# t1-power2.net
KiCad netlist of a schematic drawn in Altium Designer
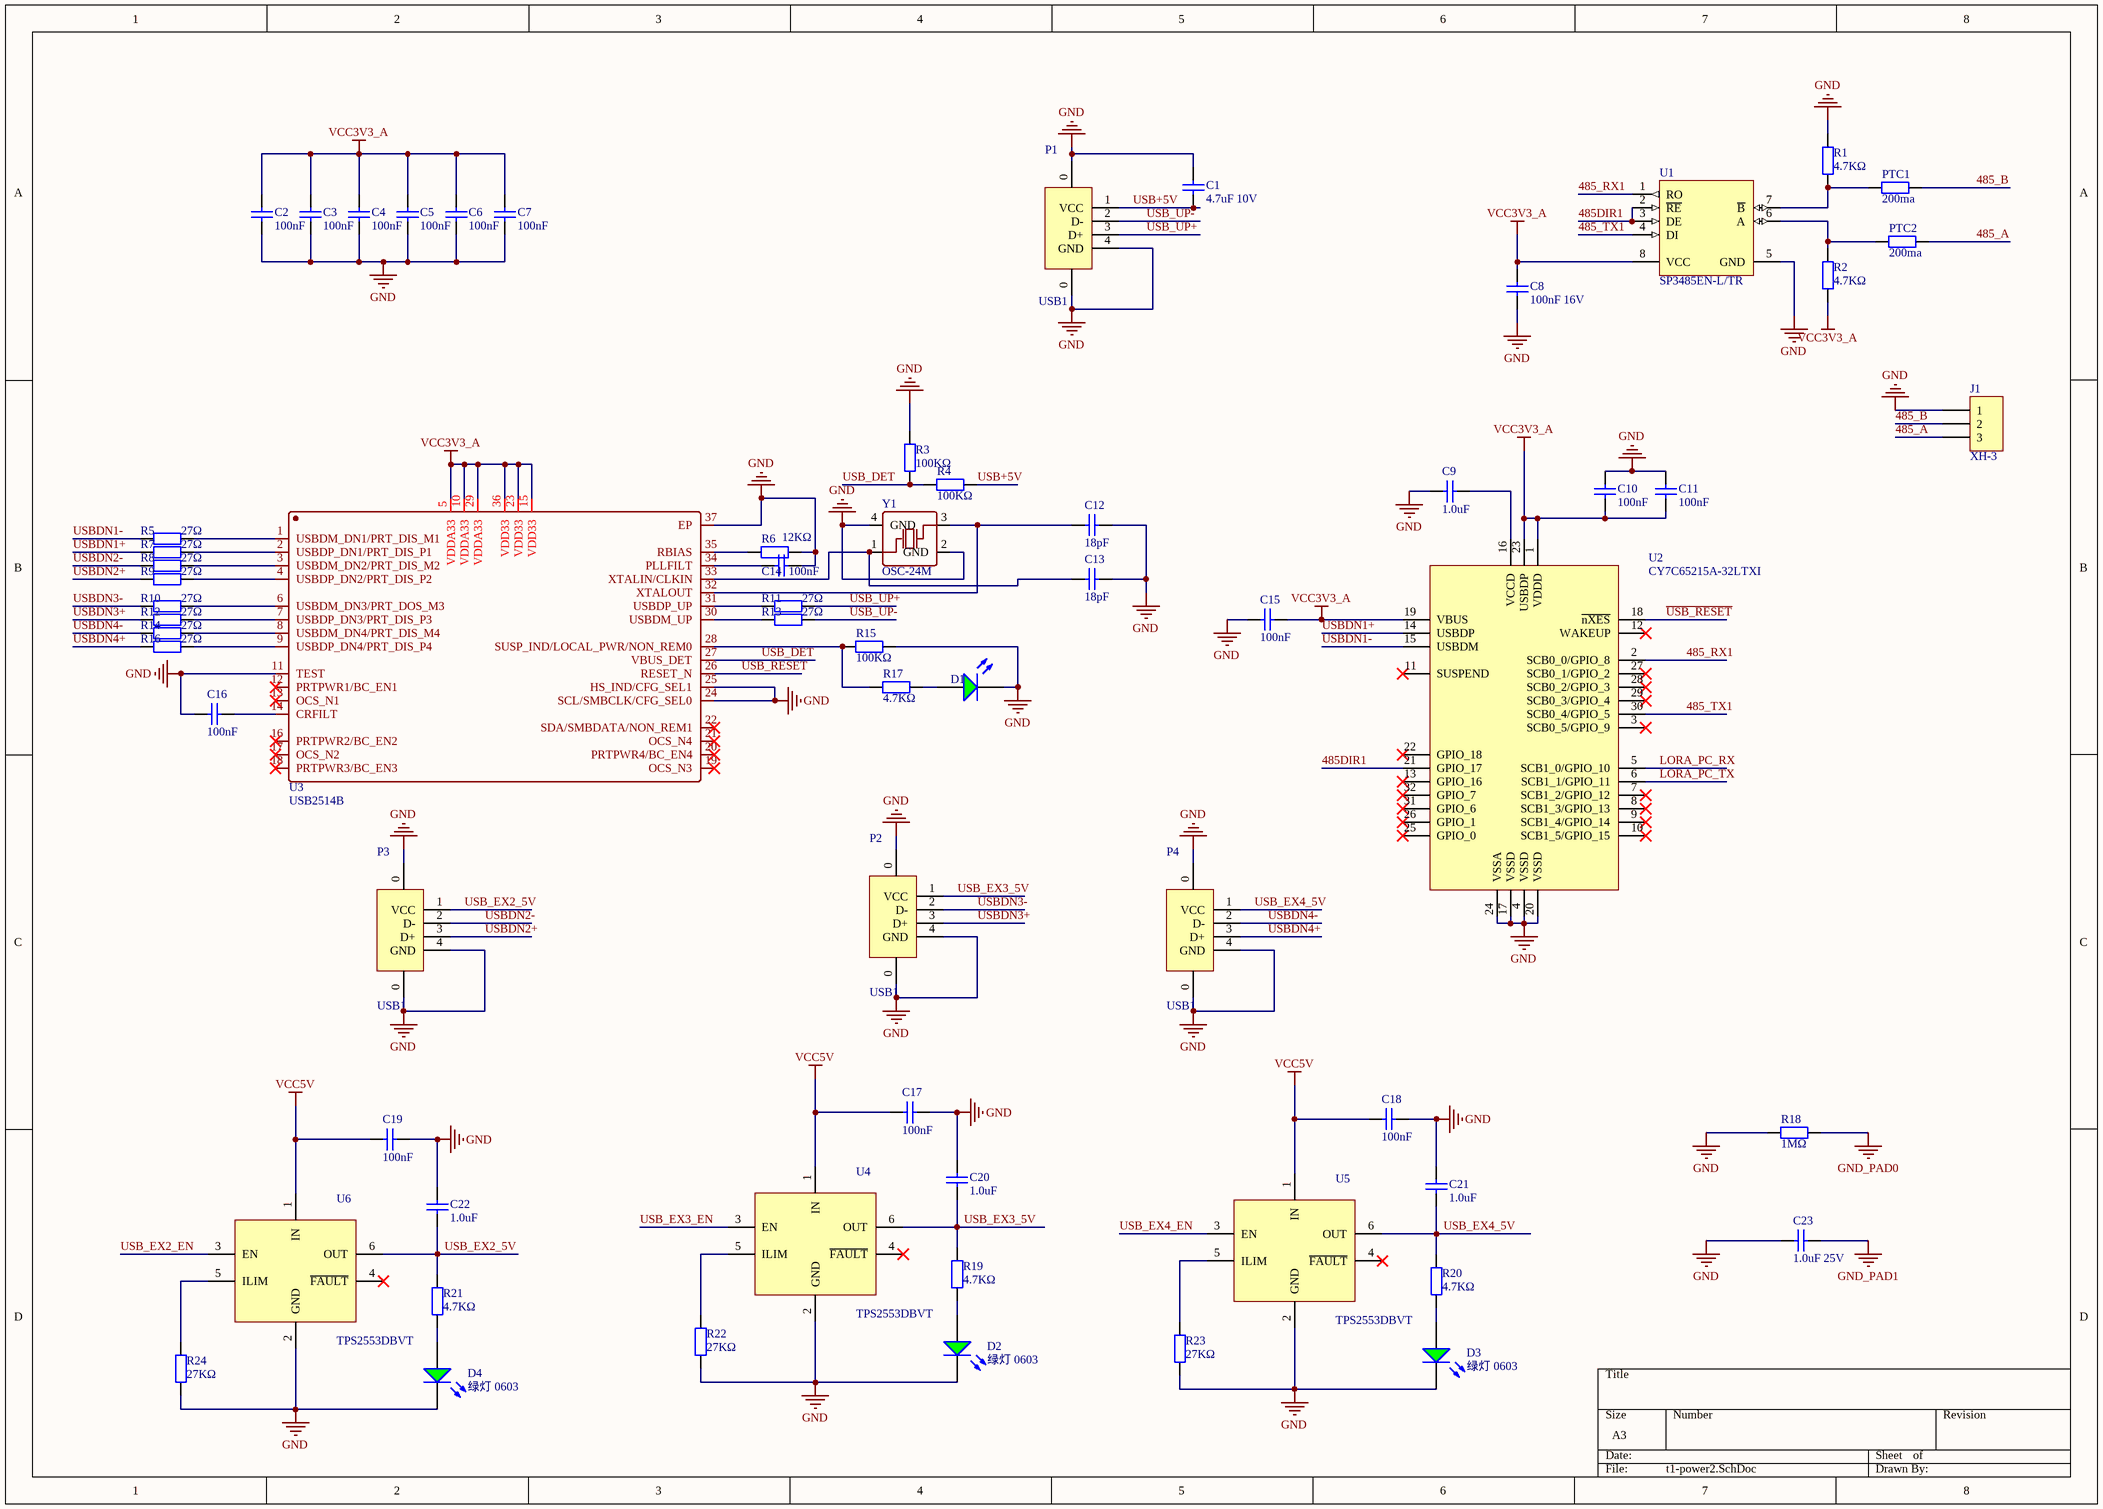
[diagram p0: t1-power2.SchDoc]

(export (version "E")
  (design (tool "Eeschema 10.0.6"))
  (components
    (comp (ref "C1")
      (value "4.7uF 10V")
      (footprint "0402_C")
      (description "贴片电容")
      (libsource (lib "AD封装2018.9.19Miscellaneous Devices LC") (part "0402 4.7uF (475) 20% 10V"))
    )
    (comp (ref "C2")
      (value "100nF")
      (footprint "0402_C")
      (description "贴片电容")
      (libsource (lib "AD封装2018.9.19Miscellaneous Devices LC") (part "0402 100nF (104) 10% 16V"))
    )
    (comp (ref "C3")
      (value "100nF")
      (footprint "0402_C")
      (description "贴片电容")
      (libsource (lib "AD封装2018.9.19Miscellaneous Devices LC") (part "0402 100nF (104) 10% 16V"))
    )
    (comp (ref "C4")
      (value "100nF")
      (footprint "0402_C")
      (description "贴片电容")
      (libsource (lib "AD封装2018.9.19Miscellaneous Devices LC") (part "0402 100nF (104) 10% 16V"))
    )
    (comp (ref "C5")
      (value "100nF")
      (footprint "0402_C")
      (description "贴片电容")
      (libsource (lib "AD封装2018.9.19Miscellaneous Devices LC") (part "0402 100nF (104) 10% 16V"))
    )
    (comp (ref "C6")
      (value "100nF")
      (footprint "0402_C")
      (description "贴片电容")
      (libsource (lib "AD封装2018.9.19Miscellaneous Devices LC") (part "0402 100nF (104) 10% 16V"))
    )
    (comp (ref "C7")
      (value "100nF")
      (footprint "0402_C")
      (description "贴片电容")
      (libsource (lib "AD封装2018.9.19Miscellaneous Devices LC") (part "0402 100nF (104) 10% 16V"))
    )
    (comp (ref "C8")
      (value "100nF 16V")
      (footprint "0402_C")
      (description "贴片电容")
      (libsource (lib "AD封装2018.9.19Miscellaneous Devices LC") (part "0402 100nF (104) 10% 16V"))
    )
    (comp (ref "C9")
      (value "1.0uF")
      (footprint "0402_C")
      (description "贴片电容")
      (libsource (lib "AD封装2018.9.19Miscellaneous Devices LC") (part "0402 1.0uF (105) 10% 25V"))
    )
    (comp (ref "C10")
      (value "100nF")
      (footprint "0402_C")
      (description "贴片电容")
      (libsource (lib "AD封装2018.9.19Miscellaneous Devices LC") (part "0402 100nF (104) 10% 16V"))
    )
    (comp (ref "C11")
      (value "100nF")
      (footprint "0402_C")
      (description "贴片电容")
      (libsource (lib "AD封装2018.9.19Miscellaneous Devices LC") (part "0402 100nF (104) 10% 16V"))
    )
    (comp (ref "C12")
      (value "18pF")
      (footprint "0402_C")
      (description "贴片电容")
      (libsource (lib "AD封装2018.9.19Miscellaneous Devices LC") (part "0402 18pF (180) 5% 50V"))
    )
    (comp (ref "C13")
      (value "18pF")
      (footprint "0402_C")
      (description "贴片电容")
      (libsource (lib "AD封装2018.9.19Miscellaneous Devices LC") (part "0402 18pF (180) 5% 50V"))
    )
    (comp (ref "C14")
      (value "100nF")
      (footprint "0402_C")
      (description "贴片电容")
      (libsource (lib "AD封装2018.9.19Miscellaneous Devices LC") (part "0402 100nF (104) 10% 16V"))
    )
    (comp (ref "C15")
      (value "100nF")
      (footprint "0402_C")
      (description "贴片电容")
      (libsource (lib "AD封装2018.9.19Miscellaneous Devices LC") (part "0402 100nF (104) 10% 16V"))
    )
    (comp (ref "C16")
      (value "100nF")
      (footprint "0402_C")
      (description "贴片电容")
      (libsource (lib "AD封装2018.9.19Miscellaneous Devices LC") (part "0402 100nF (104) 10% 16V"))
    )
    (comp (ref "C17")
      (value "100nF")
      (footprint "0402_C")
      (description "贴片电容")
      (libsource (lib "AD封装2018.9.19Miscellaneous Devices LC") (part "0402 100nF (104) 10% 16V"))
    )
    (comp (ref "C18")
      (value "100nF")
      (footprint "0402_C")
      (description "贴片电容")
      (libsource (lib "AD封装2018.9.19Miscellaneous Devices LC") (part "0402 100nF (104) 10% 16V"))
    )
    (comp (ref "C19")
      (value "100nF")
      (footprint "0402_C")
      (description "贴片电容")
      (libsource (lib "AD封装2018.9.19Miscellaneous Devices LC") (part "0402 100nF (104) 10% 16V"))
    )
    (comp (ref "C20")
      (value "1.0uF")
      (footprint "0402_C")
      (description "贴片电容")
      (libsource (lib "AD封装2018.9.19Miscellaneous Devices LC") (part "0402 1.0uF (105) 10% 25V"))
    )
    (comp (ref "C21")
      (value "1.0uF")
      (footprint "0402_C")
      (description "贴片电容")
      (libsource (lib "AD封装2018.9.19Miscellaneous Devices LC") (part "0402 1.0uF (105) 10% 25V"))
    )
    (comp (ref "C22")
      (value "1.0uF")
      (footprint "0402_C")
      (description "贴片电容")
      (libsource (lib "AD封装2018.9.19Miscellaneous Devices LC") (part "0402 1.0uF (105) 10% 25V"))
    )
    (comp (ref "C23")
      (value "1.0uF 25V")
      (footprint "0402_C")
      (description "贴片电容")
      (libsource (lib "AD封装2018.9.19Miscellaneous Devices LC") (part "0402 1.0uF (105) 10% 25V"))
    )
    (comp (ref "D1")
      (value "绿灯 0603")
      (footprint "0603_LED_S1")
      (description "发光二极管")
      (libsource (lib "AD封装2018.9.19Miscellaneous Devices LC") (part "0603 绿灯"))
    )
    (comp (ref "D2")
      (value "绿灯 0603")
      (footprint "0603_LED_S1")
      (description "发光二极管")
      (libsource (lib "AD封装2018.9.19Miscellaneous Devices LC") (part "0603 绿灯"))
    )
    (comp (ref "D3")
      (value "绿灯 0603")
      (footprint "0603_LED_S1")
      (description "发光二极管")
      (libsource (lib "AD封装2018.9.19Miscellaneous Devices LC") (part "0603 绿灯"))
    )
    (comp (ref "D4")
      (value "绿灯 0603")
      (footprint "0603_LED_S1")
      (description "发光二极管")
      (libsource (lib "AD封装2018.9.19Miscellaneous Devices LC") (part "0603 绿灯"))
    )
    (comp (ref "J1") (value "XH-3") (footprint "ph3-2.0") (libsource (lib "我的原理图库") (part "XH-3")))
    (comp (ref "P1") (value "USB1") (footprint "USB-B") (libsource (lib "我的原理图库") (part "USB1")))
    (comp (ref "P2") (value "USB1") (footprint "USB - Type A") (libsource (lib "我的原理图库") (part "USB1")))
    (comp (ref "P3") (value "USB1") (footprint "USB - Type A") (libsource (lib "我的原理图库") (part "USB1")))
    (comp (ref "P4") (value "USB1") (footprint "USB - Type A") (libsource (lib "我的原理图库") (part "USB1")))
    (comp (ref "PTC1")
      (value "200ma")
      (footprint "0603_R")
      (description "贴片电阻")
      (libsource (lib "AD封装2018.9.19Miscellaneous Devices LC") (part "0603 910Ω (9100) 1%"))
    )
    (comp (ref "PTC2")
      (value "200ma")
      (footprint "0603_R")
      (description "贴片电阻")
      (libsource (lib "AD封装2018.9.19Miscellaneous Devices LC") (part "0603 910Ω (9100) 1%"))
    )
    (comp (ref "R1")
      (value "4.7KΩ")
      (footprint "0402_R")
      (description "贴片电阻")
      (libsource (lib "AD封装2018.9.19Miscellaneous Devices LC") (part "0402 4.7KΩ (4701) 1%"))
    )
    (comp (ref "R2")
      (value "4.7KΩ")
      (footprint "0402_R")
      (description "贴片电阻")
      (libsource (lib "AD封装2018.9.19Miscellaneous Devices LC") (part "0402 4.7KΩ (4701) 1%"))
    )
    (comp (ref "R3")
      (value "100KΩ")
      (footprint "0402_R")
      (description "贴片电阻")
      (libsource (lib "") (part "0402 100KΩ (1003) 1%_1"))
    )
    (comp (ref "R4")
      (value "100KΩ")
      (footprint "0402_R")
      (description "贴片电阻")
      (libsource (lib "AD封装2018.9.19Miscellaneous Devices LC") (part "0402 100KΩ (1003) 1%"))
    )
    (comp (ref "R5")
      (value "27Ω")
      (footprint "0402_R")
      (description "贴片电阻")
      (libsource (lib "AD封装2018.9.19Miscellaneous Devices LC") (part "0402 27KΩ (2702) 1%"))
    )
    (comp (ref "R6")
      (value "12KΩ")
      (footprint "0402_R")
      (description "贴片电阻")
      (libsource (lib "AD封装2018.9.19Miscellaneous Devices LC") (part "0402 12KΩ (1202) 1%"))
    )
    (comp (ref "R7")
      (value "27Ω")
      (footprint "0402_R")
      (description "贴片电阻")
      (libsource (lib "AD封装2018.9.19Miscellaneous Devices LC") (part "0402 27KΩ (2702) 1%"))
    )
    (comp (ref "R8")
      (value "27Ω")
      (footprint "0402_R")
      (description "贴片电阻")
      (libsource (lib "AD封装2018.9.19Miscellaneous Devices LC") (part "0402 27KΩ (2702) 1%"))
    )
    (comp (ref "R9")
      (value "27Ω")
      (footprint "0402_R")
      (description "贴片电阻")
      (libsource (lib "AD封装2018.9.19Miscellaneous Devices LC") (part "0402 27KΩ (2702) 1%"))
    )
    (comp (ref "R10")
      (value "27Ω")
      (footprint "0402_R")
      (description "贴片电阻")
      (libsource (lib "AD封装2018.9.19Miscellaneous Devices LC") (part "0402 27KΩ (2702) 1%"))
    )
    (comp (ref "R11")
      (value "27Ω")
      (footprint "0402_R")
      (description "贴片电阻")
      (libsource (lib "AD封装2018.9.19Miscellaneous Devices LC") (part "0402 27KΩ (2702) 1%"))
    )
    (comp (ref "R12")
      (value "27Ω")
      (footprint "0402_R")
      (description "贴片电阻")
      (libsource (lib "AD封装2018.9.19Miscellaneous Devices LC") (part "0402 27KΩ (2702) 1%"))
    )
    (comp (ref "R13")
      (value "27Ω")
      (footprint "0402_R")
      (description "贴片电阻")
      (libsource (lib "AD封装2018.9.19Miscellaneous Devices LC") (part "0402 27KΩ (2702) 1%"))
    )
    (comp (ref "R14")
      (value "27Ω")
      (footprint "0402_R")
      (description "贴片电阻")
      (libsource (lib "AD封装2018.9.19Miscellaneous Devices LC") (part "0402 27KΩ (2702) 1%"))
    )
    (comp (ref "R15")
      (value "100KΩ")
      (footprint "0402_R")
      (description "贴片电阻")
      (libsource (lib "AD封装2018.9.19Miscellaneous Devices LC") (part "0402 100KΩ (1003) 1%"))
    )
    (comp (ref "R16")
      (value "27Ω")
      (footprint "0402_R")
      (description "贴片电阻")
      (libsource (lib "AD封装2018.9.19Miscellaneous Devices LC") (part "0402 27KΩ (2702) 1%"))
    )
    (comp (ref "R17")
      (value "4.7KΩ")
      (footprint "0402_R")
      (description "贴片电阻")
      (libsource (lib "") (part "0402 4.7KΩ (4701) 1%_1"))
    )
    (comp (ref "R18")
      (value "1MΩ")
      (footprint "0402_R")
      (description "贴片电阻")
      (libsource (lib "AD封装2018.9.19Miscellaneous Devices LC") (part "0402 1MΩ (1004) 1%"))
    )
    (comp (ref "R19")
      (value "4.7KΩ")
      (footprint "0402_R")
      (description "贴片电阻")
      (libsource (lib "AD封装2018.9.19Miscellaneous Devices LC") (part "0402 4.7KΩ (4701) 1%"))
    )
    (comp (ref "R20")
      (value "4.7KΩ")
      (footprint "0402_R")
      (description "贴片电阻")
      (libsource (lib "AD封装2018.9.19Miscellaneous Devices LC") (part "0402 4.7KΩ (4701) 1%"))
    )
    (comp (ref "R21")
      (value "4.7KΩ")
      (footprint "0402_R")
      (description "贴片电阻")
      (libsource (lib "AD封装2018.9.19Miscellaneous Devices LC") (part "0402 4.7KΩ (4701) 1%"))
    )
    (comp (ref "R22")
      (value "27KΩ")
      (footprint "0402_R")
      (description "贴片电阻")
      (libsource (lib "") (part "0402 27KΩ (2702) 1%_1"))
    )
    (comp (ref "R23")
      (value "27KΩ")
      (footprint "0402_R")
      (description "贴片电阻")
      (libsource (lib "") (part "0402 27KΩ (2702) 1%_1"))
    )
    (comp (ref "R24")
      (value "27KΩ")
      (footprint "0402_R")
      (description "贴片电阻")
      (libsource (lib "") (part "0402 27KΩ (2702) 1%_1"))
    )
    (comp (ref "U1")
      (value "SP3485EN-L/TR")
      (footprint "SOIC-8_150mil")
      (description "RS-485/RS-422")
      (libsource (lib "IC") (part "SP3485EN-L/TR_[C8963]"))
    )
    (comp (ref "U2")
      (value "CY7C65215A-32LTXI")
      (footprint "QFN-32_5X5")
      (libsource (lib "我的集成库") (part "CY7C65215A-32LTXI"))
    )
    (comp (ref "U3") (value "USB2514B") (libsource (lib "我的集成库") (part "USB2514B")))
    (comp (ref "U4")
      (value "TPS2553DBVT")
      (footprint "SOT-23-6")
      (description "SOT-23-6")
      (libsource (lib "我的集成库") (part "TPS2553DBVT"))
    )
    (comp (ref "U5")
      (value "TPS2553DBVT")
      (footprint "SOT-23-6")
      (description "SOT-23-6")
      (libsource (lib "我的集成库") (part "TPS2553DBVT"))
    )
    (comp (ref "U6")
      (value "TPS2553DBVT")
      (footprint "SOT-23-6")
      (description "SOT-23-6")
      (libsource (lib "我的集成库") (part "TPS2553DBVT"))
    )
    (comp (ref "Y1") (value "OSC-24M") (description "SMD-3225_4P") (libsource (lib "我的集成库") (part "OSC-24M")))
  )
  (nets
    (net (code "1") (name "/485DIR1") (class "Default")
      (node (ref "U1") (pin "2") (pinfunction "~{RE}_2") (pintype "input"))
      (node (ref "U1") (pin "3") (pinfunction "DE_3") (pintype "input"))
      (node (ref "U2") (pin "21") (pinfunction "GPIO_17_21") (pintype "passive"))
    )
    (net (code "2") (name "/485_A") (class "Default")
      (node (ref "J1") (pin "3") (pinfunction "3_3") (pintype "passive"))
      (node (ref "PTC2") (pin "2") (pinfunction "2_2") (pintype "passive"))
    )
    (net (code "3") (name "/485_B") (class "Default")
      (node (ref "J1") (pin "2") (pinfunction "2_2") (pintype "passive"))
      (node (ref "PTC1") (pin "2") (pinfunction "2_2") (pintype "passive"))
    )
    (net (code "4") (name "/485_RX1") (class "Default")
      (node (ref "U1") (pin "1") (pinfunction "RO_1") (pintype "output"))
      (node (ref "U2") (pin "2") (pinfunction "SCB0_0/GPIO_8_2") (pintype "passive"))
    )
    (net (code "5") (name "/485_TX1") (class "Default")
      (node (ref "U1") (pin "4") (pinfunction "DI_4") (pintype "input"))
      (node (ref "U2") (pin "30") (pinfunction "SCB0_4/GPIO_5_30") (pintype "passive"))
    )
    (net (code "6") (name "/LORA_PC_RX") (class "Default")
      (node (ref "U2") (pin "5") (pinfunction "SCB1_0/GPIO_10_5") (pintype "passive"))
    )
    (net (code "7") (name "/LORA_PC_TX") (class "Default")
      (node (ref "U2") (pin "6") (pinfunction "SCB1_1/GPIO_11_6") (pintype "passive"))
    )
    (net (code "8") (name "/USB+5V") (class "Default")
      (node (ref "C1") (pin "1") (pinfunction "1_1") (pintype "passive"))
      (node (ref "P1") (pin "1") (pinfunction "VCC_1") (pintype "passive"))
      (node (ref "R4") (pin "2") (pinfunction "2_2") (pintype "passive"))
    )
    (net (code "9") (name "/USBDN1+") (class "Default")
      (node (ref "R7") (pin "1") (pinfunction "1_1") (pintype "passive"))
      (node (ref "U2") (pin "14") (pinfunction "USBDP_14") (pintype "passive"))
    )
    (net (code "10") (name "/USBDN1-") (class "Default")
      (node (ref "R5") (pin "1") (pinfunction "1_1") (pintype "passive"))
      (node (ref "U2") (pin "15") (pinfunction "USBDM_15") (pintype "passive"))
    )
    (net (code "11") (name "/USBDN2+") (class "Default")
      (node (ref "P3") (pin "3") (pinfunction "D+_3") (pintype "passive"))
      (node (ref "R9") (pin "1") (pinfunction "1_1") (pintype "passive"))
    )
    (net (code "12") (name "/USBDN2-") (class "Default")
      (node (ref "P3") (pin "2") (pinfunction "D-_2") (pintype "passive"))
      (node (ref "R8") (pin "1") (pinfunction "1_1") (pintype "passive"))
    )
    (net (code "13") (name "/USBDN3+") (class "Default")
      (node (ref "P2") (pin "3") (pinfunction "D+_3") (pintype "passive"))
      (node (ref "R12") (pin "1") (pinfunction "1_1") (pintype "passive"))
    )
    (net (code "14") (name "/USBDN3-") (class "Default")
      (node (ref "P2") (pin "2") (pinfunction "D-_2") (pintype "passive"))
      (node (ref "R10") (pin "1") (pinfunction "1_1") (pintype "passive"))
    )
    (net (code "15") (name "/USBDN4+") (class "Default")
      (node (ref "P4") (pin "3") (pinfunction "D+_3") (pintype "passive"))
      (node (ref "R16") (pin "1") (pinfunction "1_1") (pintype "passive"))
    )
    (net (code "16") (name "/USBDN4-") (class "Default")
      (node (ref "P4") (pin "2") (pinfunction "D-_2") (pintype "passive"))
      (node (ref "R14") (pin "1") (pinfunction "1_1") (pintype "passive"))
    )
    (net (code "17") (name "/USB_DET") (class "Default")
      (node (ref "R3") (pin "1") (pinfunction "1_1") (pintype "passive"))
      (node (ref "R4") (pin "1") (pinfunction "1_1") (pintype "passive"))
      (node (ref "U3") (pin "27") (pinfunction "VBUS_DET_27") (pintype "passive"))
    )
    (net (code "18") (name "/USB_EX2_5V") (class "Default")
      (node (ref "C22") (pin "1") (pinfunction "1_1") (pintype "passive"))
      (node (ref "P3") (pin "1") (pinfunction "VCC_1") (pintype "passive"))
      (node (ref "R21") (pin "2") (pinfunction "2_2") (pintype "passive"))
      (node (ref "U6") (pin "6") (pinfunction "OUT_6") (pintype "passive"))
    )
    (net (code "19") (name "/USB_EX2_EN") (class "Default")
      (node (ref "U6") (pin "3") (pinfunction "EN_3") (pintype "passive"))
    )
    (net (code "20") (name "/USB_EX3_5V") (class "Default")
      (node (ref "C20") (pin "1") (pinfunction "1_1") (pintype "passive"))
      (node (ref "P2") (pin "1") (pinfunction "VCC_1") (pintype "passive"))
      (node (ref "R19") (pin "2") (pinfunction "2_2") (pintype "passive"))
      (node (ref "U4") (pin "6") (pinfunction "OUT_6") (pintype "passive"))
    )
    (net (code "21") (name "/USB_EX3_EN") (class "Default")
      (node (ref "U4") (pin "3") (pinfunction "EN_3") (pintype "passive"))
    )
    (net (code "22") (name "/USB_EX4_5V") (class "Default")
      (node (ref "C21") (pin "1") (pinfunction "1_1") (pintype "passive"))
      (node (ref "P4") (pin "1") (pinfunction "VCC_1") (pintype "passive"))
      (node (ref "R20") (pin "2") (pinfunction "2_2") (pintype "passive"))
      (node (ref "U5") (pin "6") (pinfunction "OUT_6") (pintype "passive"))
    )
    (net (code "23") (name "/USB_EX4_EN") (class "Default")
      (node (ref "U5") (pin "3") (pinfunction "EN_3") (pintype "passive"))
    )
    (net (code "24") (name "/USB_UP+") (class "Default")
      (node (ref "P1") (pin "3") (pinfunction "D+_3") (pintype "passive"))
      (node (ref "R11") (pin "2") (pinfunction "2_2") (pintype "passive"))
    )
    (net (code "25") (name "/USB_UP-") (class "Default")
      (node (ref "P1") (pin "2") (pinfunction "D-_2") (pintype "passive"))
      (node (ref "R13") (pin "2") (pinfunction "2_2") (pintype "passive"))
    )
    (net (code "26") (name "/~{USB_RESET}") (class "Default")
      (node (ref "U2") (pin "18") (pinfunction "~{nXES}_18") (pintype "passive"))
      (node (ref "U3") (pin "26") (pinfunction "RESET_N_26") (pintype "passive"))
    )
    (net (code "27") (name "GND") (class "Default")
      (node (ref "C1") (pin "2") (pinfunction "2_2") (pintype "passive"))
      (node (ref "C10") (pin "2") (pinfunction "2_2") (pintype "passive"))
      (node (ref "C11") (pin "2") (pinfunction "2_2") (pintype "passive"))
      (node (ref "C12") (pin "2") (pinfunction "2_2") (pintype "passive"))
      (node (ref "C13") (pin "2") (pinfunction "2_2") (pintype "passive"))
      (node (ref "C14") (pin "2") (pinfunction "2_2") (pintype "passive"))
      (node (ref "C15") (pin "2") (pinfunction "2_2") (pintype "passive"))
      (node (ref "C16") (pin "1") (pinfunction "1_1") (pintype "passive"))
      (node (ref "C17") (pin "2") (pinfunction "2_2") (pintype "passive"))
      (node (ref "C18") (pin "2") (pinfunction "2_2") (pintype "passive"))
      (node (ref "C19") (pin "2") (pinfunction "2_2") (pintype "passive"))
      (node (ref "C2") (pin "1") (pinfunction "1_1") (pintype "passive"))
      (node (ref "C20") (pin "2") (pinfunction "2_2") (pintype "passive"))
      (node (ref "C21") (pin "2") (pinfunction "2_2") (pintype "passive"))
      (node (ref "C22") (pin "2") (pinfunction "2_2") (pintype "passive"))
      (node (ref "C23") (pin "1") (pinfunction "1_1") (pintype "passive"))
      (node (ref "C3") (pin "1") (pinfunction "1_1") (pintype "passive"))
      (node (ref "C4") (pin "1") (pinfunction "1_1") (pintype "passive"))
      (node (ref "C5") (pin "1") (pinfunction "1_1") (pintype "passive"))
      (node (ref "C6") (pin "1") (pinfunction "1_1") (pintype "passive"))
      (node (ref "C7") (pin "1") (pinfunction "1_1") (pintype "passive"))
      (node (ref "C8") (pin "1") (pinfunction "1_1") (pintype "passive"))
      (node (ref "C9") (pin "1") (pinfunction "1_1") (pintype "passive"))
      (node (ref "D1") (pin "K") (pinfunction "K_K") (pintype "passive"))
      (node (ref "D2") (pin "K") (pinfunction "K_K") (pintype "passive"))
      (node (ref "D3") (pin "K") (pinfunction "K_K") (pintype "passive"))
      (node (ref "D4") (pin "K") (pinfunction "K_K") (pintype "passive"))
      (node (ref "J1") (pin "1") (pinfunction "1_1") (pintype "passive"))
      (node (ref "P1") (pin "0") (pinfunction "0_0") (pintype "passive"))
      (node (ref "P1") (pin "4") (pinfunction "GND_4") (pintype "passive"))
      (node (ref "P2") (pin "0") (pinfunction "0_0") (pintype "passive"))
      (node (ref "P2") (pin "4") (pinfunction "GND_4") (pintype "passive"))
      (node (ref "P3") (pin "0") (pinfunction "0_0") (pintype "passive"))
      (node (ref "P3") (pin "4") (pinfunction "GND_4") (pintype "passive"))
      (node (ref "P4") (pin "0") (pinfunction "0_0") (pintype "passive"))
      (node (ref "P4") (pin "4") (pinfunction "GND_4") (pintype "passive"))
      (node (ref "R1") (pin "2") (pinfunction "2_2") (pintype "passive"))
      (node (ref "R15") (pin "2") (pinfunction "2_2") (pintype "passive"))
      (node (ref "R18") (pin "1") (pinfunction "1_1") (pintype "passive"))
      (node (ref "R22") (pin "1") (pinfunction "1_1") (pintype "passive"))
      (node (ref "R23") (pin "1") (pinfunction "1_1") (pintype "passive"))
      (node (ref "R24") (pin "1") (pinfunction "1_1") (pintype "passive"))
      (node (ref "R3") (pin "2") (pinfunction "2_2") (pintype "passive"))
      (node (ref "R6") (pin "2") (pinfunction "2_2") (pintype "passive"))
      (node (ref "U1") (pin "5") (pinfunction "GND_5") (pintype "power_in"))
      (node (ref "U2") (pin "17") (pinfunction "VSSD_17") (pintype "passive"))
      (node (ref "U2") (pin "20") (pinfunction "VSSD_20") (pintype "passive"))
      (node (ref "U2") (pin "24") (pinfunction "VSSA_24") (pintype "passive"))
      (node (ref "U2") (pin "4") (pinfunction "VSSD_4") (pintype "passive"))
      (node (ref "U3") (pin "11") (pinfunction "TEST_11") (pintype "passive"))
      (node (ref "U3") (pin "24") (pinfunction "SCL/SMBCLK/CFG_SEL0_24") (pintype "passive"))
      (node (ref "U3") (pin "25") (pinfunction "HS_IND/CFG_SEL1_25") (pintype "passive"))
      (node (ref "U3") (pin "37") (pinfunction "EP_37") (pintype "passive"))
      (node (ref "U4") (pin "2") (pinfunction "GND_2") (pintype "passive"))
      (node (ref "U5") (pin "2") (pinfunction "GND_2") (pintype "passive"))
      (node (ref "U6") (pin "2") (pinfunction "GND_2") (pintype "passive"))
      (node (ref "Y1") (pin "2") (pinfunction "GND_2") (pintype "passive"))
      (node (ref "Y1") (pin "4") (pinfunction "GND_4") (pintype "passive"))
    )
    (net (code "28") (name "GND_PAD0") (class "Default")
      (node (ref "R18") (pin "2") (pinfunction "2_2") (pintype "passive"))
    )
    (net (code "29") (name "GND_PAD1") (class "Default")
      (node (ref "C23") (pin "2") (pinfunction "2_2") (pintype "passive"))
    )
    (net (code "30") (name "Net-(D1-PadA)") (class "Default")
      (node (ref "D1") (pin "A") (pinfunction "A_A") (pintype "passive"))
      (node (ref "R17") (pin "2") (pinfunction "2_2") (pintype "passive"))
    )
    (net (code "31") (name "Net-(D2-PadA)") (class "Default")
      (node (ref "D2") (pin "A") (pinfunction "A_A") (pintype "passive"))
      (node (ref "R19") (pin "1") (pinfunction "1_1") (pintype "passive"))
    )
    (net (code "32") (name "Net-(D3-PadA)") (class "Default")
      (node (ref "D3") (pin "A") (pinfunction "A_A") (pintype "passive"))
      (node (ref "R20") (pin "1") (pinfunction "1_1") (pintype "passive"))
    )
    (net (code "33") (name "Net-(D4-PadA)") (class "Default")
      (node (ref "D4") (pin "A") (pinfunction "A_A") (pintype "passive"))
      (node (ref "R21") (pin "1") (pinfunction "1_1") (pintype "passive"))
    )
    (net (code "34") (name "Net-(U1-A)") (class "Default")
      (node (ref "PTC2") (pin "1") (pinfunction "1_1") (pintype "passive"))
      (node (ref "R2") (pin "2") (pinfunction "2_2") (pintype "passive"))
      (node (ref "U1") (pin "6") (pinfunction "A_6") (pintype "bidirectional"))
    )
    (net (code "35") (name "Net-(U1-~{B})") (class "Default")
      (node (ref "PTC1") (pin "1") (pinfunction "1_1") (pintype "passive"))
      (node (ref "R1") (pin "1") (pinfunction "1_1") (pintype "passive"))
      (node (ref "U1") (pin "7") (pinfunction "~{B}_7") (pintype "bidirectional"))
    )
    (net (code "36") (name "Net-(U2-VCCD)") (class "Default")
      (node (ref "C9") (pin "2") (pinfunction "2_2") (pintype "passive"))
      (node (ref "U2") (pin "16") (pinfunction "VCCD_16") (pintype "passive"))
    )
    (net (code "37") (name "Net-(U3-CRFILT)") (class "Default")
      (node (ref "C16") (pin "2") (pinfunction "2_2") (pintype "passive"))
      (node (ref "U3") (pin "14") (pinfunction "CRFILT_14") (pintype "passive"))
    )
    (net (code "38") (name "Net-(U3-PLLFILT)") (class "Default")
      (node (ref "C14") (pin "1") (pinfunction "1_1") (pintype "passive"))
      (node (ref "U3") (pin "34") (pinfunction "PLLFILT_34") (pintype "passive"))
    )
    (net (code "39") (name "Net-(U3-RBIAS)") (class "Default")
      (node (ref "R6") (pin "1") (pinfunction "1_1") (pintype "passive"))
      (node (ref "U3") (pin "35") (pinfunction "RBIAS_35") (pintype "passive"))
    )
    (net (code "40") (name "Net-(U3-SUSP_IND{slash}LOCAL_PWR{slash}NON_REM0)") (class "Default")
      (node (ref "R15") (pin "1") (pinfunction "1_1") (pintype "passive"))
      (node (ref "R17") (pin "1") (pinfunction "1_1") (pintype "passive"))
      (node (ref "U3") (pin "28") (pinfunction "SUSP_IND/LOCAL_PWR/NON_REM0_28") (pintype "passive"))
    )
    (net (code "41") (name "Net-(U3-USBDM_DN1{slash}PRT_DIS_M1)") (class "Default")
      (node (ref "R5") (pin "2") (pinfunction "2_2") (pintype "passive"))
      (node (ref "U3") (pin "1") (pinfunction "USBDM_DN1/PRT_DIS_M1_1") (pintype "passive"))
    )
    (net (code "42") (name "Net-(U3-USBDM_DN2{slash}PRT_DIS_M2)") (class "Default")
      (node (ref "R8") (pin "2") (pinfunction "2_2") (pintype "passive"))
      (node (ref "U3") (pin "3") (pinfunction "USBDM_DN2/PRT_DIS_M2_3") (pintype "passive"))
    )
    (net (code "43") (name "Net-(U3-USBDM_DN3{slash}PRT_DOS_M3)") (class "Default")
      (node (ref "R10") (pin "2") (pinfunction "2_2") (pintype "passive"))
      (node (ref "U3") (pin "6") (pinfunction "USBDM_DN3/PRT_DOS_M3_6") (pintype "passive"))
    )
    (net (code "44") (name "Net-(U3-USBDM_DN4{slash}PRT_DIS_M4)") (class "Default")
      (node (ref "R14") (pin "2") (pinfunction "2_2") (pintype "passive"))
      (node (ref "U3") (pin "8") (pinfunction "USBDM_DN4/PRT_DIS_M4_8") (pintype "passive"))
    )
    (net (code "45") (name "Net-(U3-USBDM_UP)") (class "Default")
      (node (ref "R13") (pin "1") (pinfunction "1_1") (pintype "passive"))
      (node (ref "U3") (pin "30") (pinfunction "USBDM_UP_30") (pintype "passive"))
    )
    (net (code "46") (name "Net-(U3-USBDP_DN1{slash}PRT_DIS_P1)") (class "Default")
      (node (ref "R7") (pin "2") (pinfunction "2_2") (pintype "passive"))
      (node (ref "U3") (pin "2") (pinfunction "USBDP_DN1/PRT_DIS_P1_2") (pintype "passive"))
    )
    (net (code "47") (name "Net-(U3-USBDP_DN2{slash}PRT_DIS_P2)") (class "Default")
      (node (ref "R9") (pin "2") (pinfunction "2_2") (pintype "passive"))
      (node (ref "U3") (pin "4") (pinfunction "USBDP_DN2/PRT_DIS_P2_4") (pintype "passive"))
    )
    (net (code "48") (name "Net-(U3-USBDP_DN3{slash}PRT_DIS_P3)") (class "Default")
      (node (ref "R12") (pin "2") (pinfunction "2_2") (pintype "passive"))
      (node (ref "U3") (pin "7") (pinfunction "USBDP_DN3/PRT_DIS_P3_7") (pintype "passive"))
    )
    (net (code "49") (name "Net-(U3-USBDP_DN4{slash}PRT_DIS_P4)") (class "Default")
      (node (ref "R16") (pin "2") (pinfunction "2_2") (pintype "passive"))
      (node (ref "U3") (pin "9") (pinfunction "USBDP_DN4/PRT_DIS_P4_9") (pintype "passive"))
    )
    (net (code "50") (name "Net-(U3-USBDP_UP)") (class "Default")
      (node (ref "R11") (pin "1") (pinfunction "1_1") (pintype "passive"))
      (node (ref "U3") (pin "31") (pinfunction "USBDP_UP_31") (pintype "passive"))
    )
    (net (code "51") (name "Net-(U3-XTALIN{slash}CLKIN)") (class "Default")
      (node (ref "C13") (pin "1") (pinfunction "1_1") (pintype "passive"))
      (node (ref "U3") (pin "33") (pinfunction "XTALIN/CLKIN_33") (pintype "passive"))
      (node (ref "Y1") (pin "1") (pinfunction "OSC1_1") (pintype "passive"))
    )
    (net (code "52") (name "Net-(U3-XTALOUT)") (class "Default")
      (node (ref "C12") (pin "1") (pinfunction "1_1") (pintype "passive"))
      (node (ref "U3") (pin "32") (pinfunction "XTALOUT_32") (pintype "passive"))
      (node (ref "Y1") (pin "3") (pinfunction "OSC2_3") (pintype "passive"))
    )
    (net (code "53") (name "Net-(U4-ILIM)") (class "Default")
      (node (ref "R22") (pin "2") (pinfunction "2_2") (pintype "passive"))
      (node (ref "U4") (pin "5") (pinfunction "ILIM_5") (pintype "passive"))
    )
    (net (code "54") (name "Net-(U5-ILIM)") (class "Default")
      (node (ref "R23") (pin "2") (pinfunction "2_2") (pintype "passive"))
      (node (ref "U5") (pin "5") (pinfunction "ILIM_5") (pintype "passive"))
    )
    (net (code "55") (name "Net-(U6-ILIM)") (class "Default")
      (node (ref "R24") (pin "2") (pinfunction "2_2") (pintype "passive"))
      (node (ref "U6") (pin "5") (pinfunction "ILIM_5") (pintype "passive"))
    )
    (net (code "56") (name "VCC3V3_A") (class "Default")
      (node (ref "C10") (pin "1") (pinfunction "1_1") (pintype "passive"))
      (node (ref "C11") (pin "1") (pinfunction "1_1") (pintype "passive"))
      (node (ref "C15") (pin "1") (pinfunction "1_1") (pintype "passive"))
      (node (ref "C2") (pin "2") (pinfunction "2_2") (pintype "passive"))
      (node (ref "C3") (pin "2") (pinfunction "2_2") (pintype "passive"))
      (node (ref "C4") (pin "2") (pinfunction "2_2") (pintype "passive"))
      (node (ref "C5") (pin "2") (pinfunction "2_2") (pintype "passive"))
      (node (ref "C6") (pin "2") (pinfunction "2_2") (pintype "passive"))
      (node (ref "C7") (pin "2") (pinfunction "2_2") (pintype "passive"))
      (node (ref "C8") (pin "2") (pinfunction "2_2") (pintype "passive"))
      (node (ref "R2") (pin "1") (pinfunction "1_1") (pintype "passive"))
      (node (ref "U1") (pin "8") (pinfunction "VCC_8") (pintype "power_in"))
      (node (ref "U2") (pin "1") (pinfunction "VDDD_1") (pintype "passive"))
      (node (ref "U2") (pin "19") (pinfunction "VBUS_19") (pintype "passive"))
      (node (ref "U2") (pin "23") (pinfunction "USBDP_23") (pintype "passive"))
      (node (ref "U3") (pin "10") (pinfunction "VDDA33_10") (pintype "passive"))
      (node (ref "U3") (pin "15") (pinfunction "VDD33_15") (pintype "passive"))
      (node (ref "U3") (pin "23") (pinfunction "VDD33_23") (pintype "passive"))
      (node (ref "U3") (pin "29") (pinfunction "VDDA33_29") (pintype "passive"))
      (node (ref "U3") (pin "36") (pinfunction "VDD33_36") (pintype "passive"))
      (node (ref "U3") (pin "5") (pinfunction "VDDA33_5") (pintype "passive"))
    )
    (net (code "57") (name "VCC5V") (class "Default")
      (node (ref "C17") (pin "1") (pinfunction "1_1") (pintype "passive"))
      (node (ref "C18") (pin "1") (pinfunction "1_1") (pintype "passive"))
      (node (ref "C19") (pin "1") (pinfunction "1_1") (pintype "passive"))
      (node (ref "U4") (pin "1") (pinfunction "IN_1") (pintype "passive"))
      (node (ref "U5") (pin "1") (pinfunction "IN_1") (pintype "passive"))
      (node (ref "U6") (pin "1") (pinfunction "IN_1") (pintype "passive"))
    )
    (net (code "58") (name "unconnected-(P1-Pad0)") (class "Default")
      (node (ref "P1") (pin "0") (pinfunction "0_0") (pintype "passive"))
    )
    (net (code "59") (name "unconnected-(P2-Pad0)") (class "Default")
      (node (ref "P2") (pin "0") (pinfunction "0_0") (pintype "passive"))
    )
    (net (code "60") (name "unconnected-(P3-Pad0)") (class "Default")
      (node (ref "P3") (pin "0") (pinfunction "0_0") (pintype "passive"))
    )
    (net (code "61") (name "unconnected-(P4-Pad0)") (class "Default")
      (node (ref "P4") (pin "0") (pinfunction "0_0") (pintype "passive"))
    )
    (net (code "62") (name "unconnected-(U2-GPIO_0-Pad25)") (class "Default")
      (node (ref "U2") (pin "25") (pinfunction "GPIO_0_25") (pintype "passive+no_connect"))
    )
    (net (code "63") (name "unconnected-(U2-GPIO_1-Pad26)") (class "Default")
      (node (ref "U2") (pin "26") (pinfunction "GPIO_1_26") (pintype "passive+no_connect"))
    )
    (net (code "64") (name "unconnected-(U2-GPIO_6-Pad31)") (class "Default")
      (node (ref "U2") (pin "31") (pinfunction "GPIO_6_31") (pintype "passive+no_connect"))
    )
    (net (code "65") (name "unconnected-(U2-GPIO_7-Pad32)") (class "Default")
      (node (ref "U2") (pin "32") (pinfunction "GPIO_7_32") (pintype "passive+no_connect"))
    )
    (net (code "66") (name "unconnected-(U2-GPIO_16-Pad13)") (class "Default")
      (node (ref "U2") (pin "13") (pinfunction "GPIO_16_13") (pintype "passive+no_connect"))
    )
    (net (code "67") (name "unconnected-(U2-GPIO_18-Pad22)") (class "Default")
      (node (ref "U2") (pin "22") (pinfunction "GPIO_18_22") (pintype "passive+no_connect"))
    )
    (net (code "68") (name "unconnected-(U2-SCB0_1{slash}GPIO_2-Pad27)") (class "Default")
      (node (ref "U2") (pin "27") (pinfunction "SCB0_1/GPIO_2_27") (pintype "passive+no_connect"))
    )
    (net (code "69") (name "unconnected-(U2-SCB0_2{slash}GPIO_3-Pad28)") (class "Default")
      (node (ref "U2") (pin "28") (pinfunction "SCB0_2/GPIO_3_28") (pintype "passive+no_connect"))
    )
    (net (code "70") (name "unconnected-(U2-SCB0_3{slash}GPIO_4-Pad29)") (class "Default")
      (node (ref "U2") (pin "29") (pinfunction "SCB0_3/GPIO_4_29") (pintype "passive+no_connect"))
    )
    (net (code "71") (name "unconnected-(U2-SCB0_5{slash}GPIO_9-Pad3)") (class "Default")
      (node (ref "U2") (pin "3") (pinfunction "SCB0_5/GPIO_9_3") (pintype "passive+no_connect"))
    )
    (net (code "72") (name "unconnected-(U2-SCB1_2{slash}GPIO_12-Pad7)") (class "Default")
      (node (ref "U2") (pin "7") (pinfunction "SCB1_2/GPIO_12_7") (pintype "passive+no_connect"))
    )
    (net (code "73") (name "unconnected-(U2-SCB1_3{slash}GPIO_13-Pad8)") (class "Default")
      (node (ref "U2") (pin "8") (pinfunction "SCB1_3/GPIO_13_8") (pintype "passive+no_connect"))
    )
    (net (code "74") (name "unconnected-(U2-SCB1_4{slash}GPIO_14-Pad9)") (class "Default")
      (node (ref "U2") (pin "9") (pinfunction "SCB1_4/GPIO_14_9") (pintype "passive+no_connect"))
    )
    (net (code "75") (name "unconnected-(U2-SCB1_5{slash}GPIO_15-Pad10)") (class "Default")
      (node (ref "U2") (pin "10") (pinfunction "SCB1_5/GPIO_15_10") (pintype "passive+no_connect"))
    )
    (net (code "76") (name "unconnected-(U2-SUSPEND-Pad11)") (class "Default")
      (node (ref "U2") (pin "11") (pinfunction "SUSPEND_11") (pintype "passive+no_connect"))
    )
    (net (code "77") (name "unconnected-(U2-WAKEUP-Pad12)") (class "Default")
      (node (ref "U2") (pin "12") (pinfunction "WAKEUP_12") (pintype "passive+no_connect"))
    )
    (net (code "78") (name "unconnected-(U3-OCS_N1-Pad13)") (class "Default")
      (node (ref "U3") (pin "13") (pinfunction "OCS_N1_13") (pintype "passive+no_connect"))
    )
    (net (code "79") (name "unconnected-(U3-OCS_N2-Pad17)") (class "Default")
      (node (ref "U3") (pin "17") (pinfunction "OCS_N2_17") (pintype "passive+no_connect"))
    )
    (net (code "80") (name "unconnected-(U3-OCS_N3-Pad19)") (class "Default")
      (node (ref "U3") (pin "19") (pinfunction "OCS_N3_19") (pintype "passive+no_connect"))
    )
    (net (code "81") (name "unconnected-(U3-OCS_N4-Pad21)") (class "Default")
      (node (ref "U3") (pin "21") (pinfunction "OCS_N4_21") (pintype "passive+no_connect"))
    )
    (net (code "82") (name "unconnected-(U3-PRTPWR1{slash}BC_EN1-Pad12)") (class "Default")
      (node (ref "U3") (pin "12") (pinfunction "PRTPWR1/BC_EN1_12") (pintype "passive+no_connect"))
    )
    (net (code "83") (name "unconnected-(U3-PRTPWR2{slash}BC_EN2-Pad16)") (class "Default")
      (node (ref "U3") (pin "16") (pinfunction "PRTPWR2/BC_EN2_16") (pintype "passive+no_connect"))
    )
    (net (code "84") (name "unconnected-(U3-PRTPWR3{slash}BC_EN3-Pad18)") (class "Default")
      (node (ref "U3") (pin "18") (pinfunction "PRTPWR3/BC_EN3_18") (pintype "passive+no_connect"))
    )
    (net (code "85") (name "unconnected-(U3-PRTPWR4{slash}BC_EN4-Pad20)") (class "Default")
      (node (ref "U3") (pin "20") (pinfunction "PRTPWR4/BC_EN4_20") (pintype "passive+no_connect"))
    )
    (net (code "86") (name "unconnected-(U3-SDA{slash}SMBDATA{slash}NON_REM1-Pad22)") (class "Default")
      (node (ref "U3") (pin "22") (pinfunction "SDA/SMBDATA/NON_REM1_22") (pintype "passive+no_connect"))
    )
    (net (code "87") (name "unconnected-(U4-~{FAULT}-Pad4)") (class "Default")
      (node (ref "U4") (pin "4") (pinfunction "~{FAULT}_4") (pintype "passive+no_connect"))
    )
    (net (code "88") (name "unconnected-(U5-~{FAULT}-Pad4)") (class "Default")
      (node (ref "U5") (pin "4") (pinfunction "~{FAULT}_4") (pintype "passive+no_connect"))
    )
    (net (code "89") (name "unconnected-(U6-~{FAULT}-Pad4)") (class "Default")
      (node (ref "U6") (pin "4") (pinfunction "~{FAULT}_4") (pintype "passive+no_connect"))
    )
  )
)
